# Commu02.net
KiCad netlist of a schematic drawn in Altium Designer
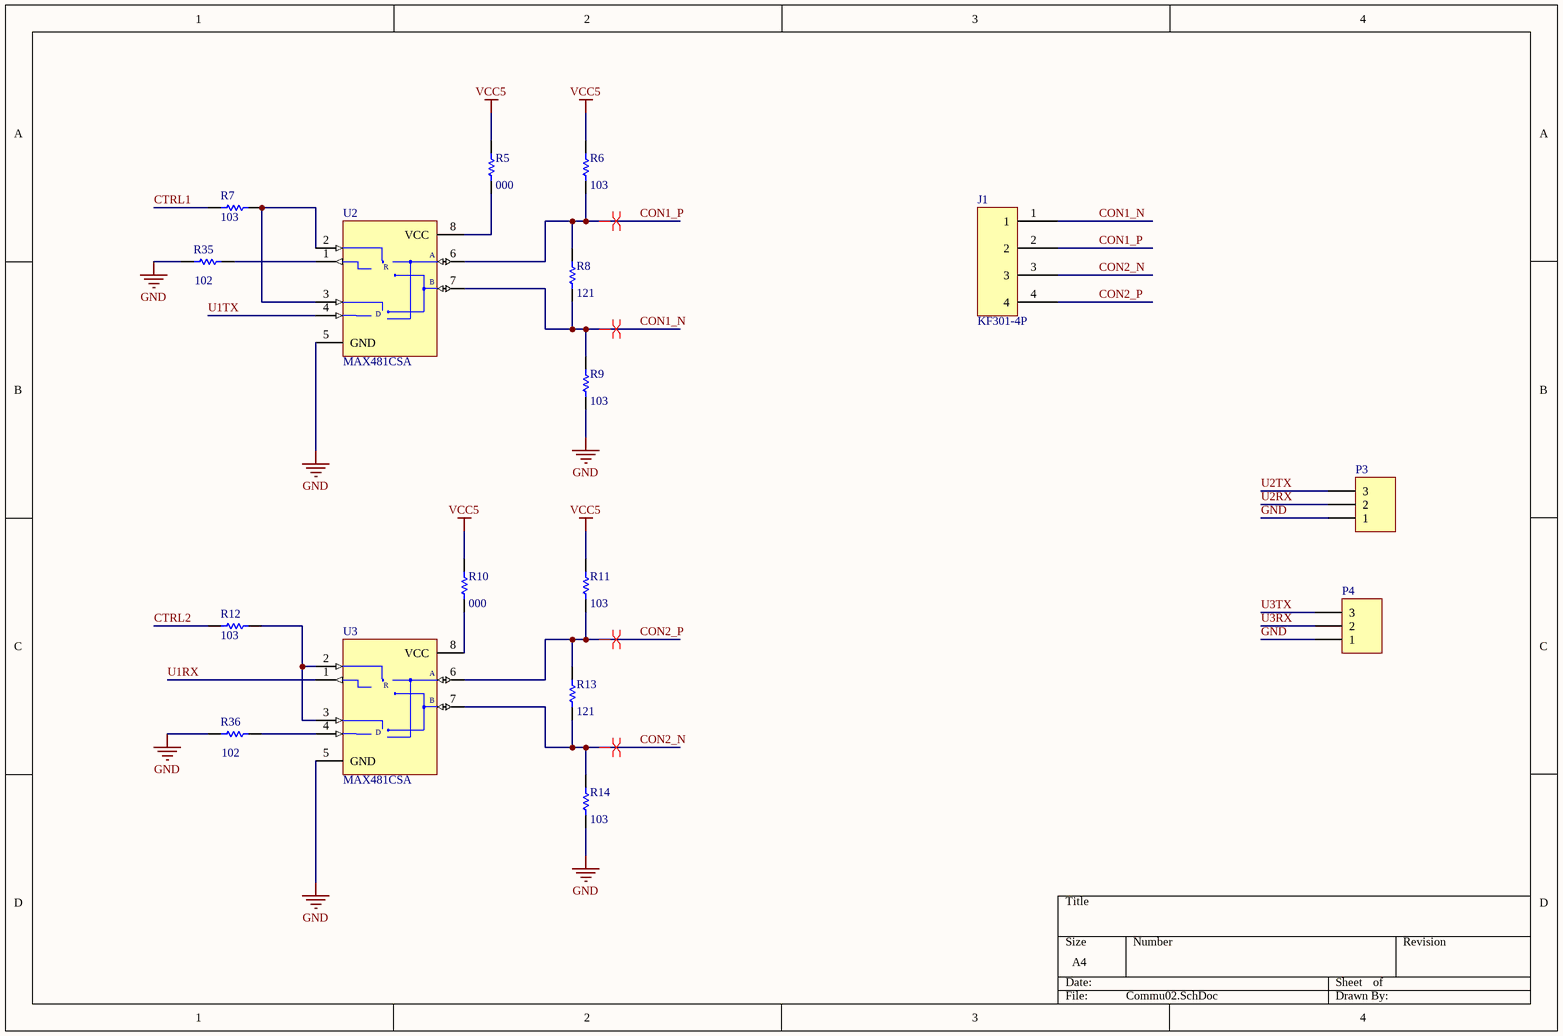
[diagram p0: Commu02.SchDoc]

(export (version "E")
  (design (tool "Eeschema 10.0.6"))
  (components
    (comp (ref "J1") (value "KF301-4P") (footprint "KF301-4P") (libsource (lib "CHK-I") (part "KF301-4P")))
    (comp (ref "P3")
      (value "Header 3")
      (footprint "HDR1X3")
      (description "Header, 3-Pin")
      (fields (field (name "PUBLISHER") "Altium Limited"))
      (libsource (lib "Miscellaneous Connectors") (part "Header 3"))
    )
    (comp (ref "P4")
      (value "Header 3")
      (footprint "HDR1X3")
      (description "Header, 3-Pin")
      (fields (field (name "PUBLISHER") "Altium Limited"))
      (libsource (lib "Miscellaneous Connectors") (part "Header 3"))
    )
    (comp (ref "R5")
      (value "000")
      (footprint "1206")
      (description "Semiconductor Resistor")
      (fields (field (name "Comment") "Res Semi") (field (name "PUBLISHER") "Altium Limited"))
      (libsource (lib "Miscellaneous Devices") (part "Res Semi"))
    )
    (comp (ref "R6")
      (value "103")
      (footprint "1206")
      (description "Semiconductor Resistor")
      (fields (field (name "Comment") "Res Semi") (field (name "PUBLISHER") "Altium Limited"))
      (libsource (lib "Miscellaneous Devices") (part "Res Semi"))
    )
    (comp (ref "R7")
      (value "103")
      (footprint "1206")
      (description "Semiconductor Resistor")
      (fields (field (name "Comment") "Res Semi") (field (name "PUBLISHER") "Altium Limited"))
      (libsource (lib "Miscellaneous Devices") (part "Res Semi"))
    )
    (comp (ref "R8")
      (value "121")
      (footprint "1206")
      (description "Semiconductor Resistor")
      (fields (field (name "Comment") "Res Semi") (field (name "PUBLISHER") "Altium Limited"))
      (libsource (lib "Miscellaneous Devices") (part "Res Semi"))
    )
    (comp (ref "R9")
      (value "103")
      (footprint "1206")
      (description "Semiconductor Resistor")
      (fields (field (name "Comment") "Res Semi") (field (name "PUBLISHER") "Altium Limited"))
      (libsource (lib "Miscellaneous Devices") (part "Res Semi"))
    )
    (comp (ref "R10")
      (value "000")
      (footprint "1206")
      (description "Semiconductor Resistor")
      (fields (field (name "Comment") "Res Semi") (field (name "PUBLISHER") "Altium Limited"))
      (libsource (lib "Miscellaneous Devices") (part "Res Semi"))
    )
    (comp (ref "R11")
      (value "103")
      (footprint "1206")
      (description "Semiconductor Resistor")
      (fields (field (name "Comment") "Res Semi") (field (name "PUBLISHER") "Altium Limited"))
      (libsource (lib "Miscellaneous Devices") (part "Res Semi"))
    )
    (comp (ref "R12")
      (value "103")
      (footprint "1206")
      (description "Semiconductor Resistor")
      (fields (field (name "Comment") "Res Semi") (field (name "PUBLISHER") "Altium Limited"))
      (libsource (lib "Miscellaneous Devices") (part "Res Semi"))
    )
    (comp (ref "R13")
      (value "121")
      (footprint "1206")
      (description "Semiconductor Resistor")
      (fields (field (name "Comment") "Res Semi") (field (name "PUBLISHER") "Altium Limited"))
      (libsource (lib "Miscellaneous Devices") (part "Res Semi"))
    )
    (comp (ref "R14")
      (value "103")
      (footprint "1206")
      (description "Semiconductor Resistor")
      (fields (field (name "Comment") "Res Semi") (field (name "PUBLISHER") "Altium Limited"))
      (libsource (lib "Miscellaneous Devices") (part "Res Semi"))
    )
    (comp (ref "R35")
      (value "102")
      (description "Semiconductor Resistor")
      (fields (field (name "Comment") "Res Semi") (field (name "PUBLISHER") "Altium Limited"))
      (libsource (lib "Miscellaneous Devices") (part "Res Semi"))
    )
    (comp (ref "R36")
      (value "102")
      (description "Semiconductor Resistor")
      (fields (field (name "Comment") "Res Semi") (field (name "PUBLISHER") "Altium Limited"))
      (libsource (lib "Miscellaneous Devices") (part "Res Semi"))
    )
    (comp (ref "U2")
      (value "MAX481CSA")
      (footprint "NSO8_M")
      (description "Low-Power, Slew-Rate-Limited RS-485/RS-422 Transceiver")
      (fields (field (name "PUBLISHER") "Altium Limited"))
      (libsource (lib "Maxim Communication Transceiver") (part "MAX481CSA"))
    )
    (comp (ref "U3")
      (value "MAX481CSA")
      (footprint "NSO8_M")
      (description "Low-Power, Slew-Rate-Limited RS-485/RS-422 Transceiver")
      (fields (field (name "PUBLISHER") "Altium Limited"))
      (libsource (lib "Maxim Communication Transceiver") (part "MAX481CSA"))
    )
  )
  (nets
    (net (code "1") (name "/CON1_N") (class "Default")
      (node (ref "J1") (pin "1") (pinfunction "1_1") (pintype "passive"))
      (node (ref "R8") (pin "1") (pinfunction "1_1") (pintype "passive"))
      (node (ref "R9") (pin "2") (pinfunction "2_2") (pintype "passive"))
      (node (ref "U2") (pin "7") (pinfunction "B_7") (pintype "bidirectional"))
    )
    (net (code "2") (name "/CON1_P") (class "Default")
      (node (ref "J1") (pin "2") (pinfunction "2_2") (pintype "passive"))
      (node (ref "R6") (pin "1") (pinfunction "1_1") (pintype "passive"))
      (node (ref "R8") (pin "2") (pinfunction "2_2") (pintype "passive"))
      (node (ref "U2") (pin "6") (pinfunction "A_6") (pintype "bidirectional"))
    )
    (net (code "3") (name "/CON2_N") (class "Default")
      (node (ref "J1") (pin "3") (pinfunction "3_3") (pintype "passive"))
      (node (ref "R13") (pin "1") (pinfunction "1_1") (pintype "passive"))
      (node (ref "R14") (pin "2") (pinfunction "2_2") (pintype "passive"))
      (node (ref "U3") (pin "7") (pinfunction "B_7") (pintype "bidirectional"))
    )
    (net (code "4") (name "/CON2_P") (class "Default")
      (node (ref "J1") (pin "4") (pinfunction "4_4") (pintype "passive"))
      (node (ref "R11") (pin "1") (pinfunction "1_1") (pintype "passive"))
      (node (ref "R13") (pin "2") (pinfunction "2_2") (pintype "passive"))
      (node (ref "U3") (pin "6") (pinfunction "A_6") (pintype "bidirectional"))
    )
    (net (code "5") (name "/CTRL1") (class "Default")
      (node (ref "R7") (pin "2") (pinfunction "2_2") (pintype "passive"))
    )
    (net (code "6") (name "/CTRL2") (class "Default")
      (node (ref "R12") (pin "2") (pinfunction "2_2") (pintype "passive"))
    )
    (net (code "7") (name "/U1RX") (class "Default")
      (node (ref "U3") (pin "1") (pinfunction "RO_1") (pintype "output"))
    )
    (net (code "8") (name "/U1TX") (class "Default")
      (node (ref "U2") (pin "4") (pinfunction "DI_4") (pintype "input"))
    )
    (net (code "9") (name "/U2RX") (class "Default")
      (node (ref "P3") (pin "2") (pinfunction "2_2") (pintype "passive"))
    )
    (net (code "10") (name "/U2TX") (class "Default")
      (node (ref "P3") (pin "3") (pinfunction "3_3") (pintype "passive"))
    )
    (net (code "11") (name "/U3RX") (class "Default")
      (node (ref "P4") (pin "2") (pinfunction "2_2") (pintype "passive"))
    )
    (net (code "12") (name "/U3TX") (class "Default")
      (node (ref "P4") (pin "3") (pinfunction "3_3") (pintype "passive"))
    )
    (net (code "13") (name "GND") (class "Default")
      (node (ref "P3") (pin "1") (pinfunction "1_1") (pintype "passive"))
      (node (ref "P4") (pin "1") (pinfunction "1_1") (pintype "passive"))
      (node (ref "R14") (pin "1") (pinfunction "1_1") (pintype "passive"))
      (node (ref "R35") (pin "2") (pinfunction "2_2") (pintype "passive"))
      (node (ref "R36") (pin "2") (pinfunction "2_2") (pintype "passive"))
      (node (ref "R9") (pin "1") (pinfunction "1_1") (pintype "passive"))
      (node (ref "U2") (pin "5") (pinfunction "GND_5") (pintype "power_in"))
      (node (ref "U3") (pin "5") (pinfunction "GND_5") (pintype "power_in"))
    )
    (net (code "14") (name "Net-(U2-DE)") (class "Default")
      (node (ref "R7") (pin "1") (pinfunction "1_1") (pintype "passive"))
      (node (ref "U2") (pin "2") (pinfunction "~{RE}_2") (pintype "input"))
      (node (ref "U2") (pin "3") (pinfunction "DE_3") (pintype "input"))
    )
    (net (code "15") (name "Net-(U2-RO)") (class "Default")
      (node (ref "R35") (pin "1") (pinfunction "1_1") (pintype "passive"))
      (node (ref "U2") (pin "1") (pinfunction "RO_1") (pintype "output"))
    )
    (net (code "16") (name "Net-(U2-VCC)") (class "Default")
      (node (ref "R5") (pin "1") (pinfunction "1_1") (pintype "passive"))
      (node (ref "U2") (pin "8") (pinfunction "VCC_8") (pintype "power_in"))
    )
    (net (code "17") (name "Net-(U3-DE)") (class "Default")
      (node (ref "R12") (pin "1") (pinfunction "1_1") (pintype "passive"))
      (node (ref "U3") (pin "2") (pinfunction "~{RE}_2") (pintype "input"))
      (node (ref "U3") (pin "3") (pinfunction "DE_3") (pintype "input"))
    )
    (net (code "18") (name "Net-(U3-DI)") (class "Default")
      (node (ref "R36") (pin "1") (pinfunction "1_1") (pintype "passive"))
      (node (ref "U3") (pin "4") (pinfunction "DI_4") (pintype "input"))
    )
    (net (code "19") (name "Net-(U3-VCC)") (class "Default")
      (node (ref "R10") (pin "1") (pinfunction "1_1") (pintype "passive"))
      (node (ref "U3") (pin "8") (pinfunction "VCC_8") (pintype "power_in"))
    )
    (net (code "20") (name "VCC5") (class "Default")
      (node (ref "R10") (pin "2") (pinfunction "2_2") (pintype "passive"))
      (node (ref "R11") (pin "2") (pinfunction "2_2") (pintype "passive"))
      (node (ref "R5") (pin "2") (pinfunction "2_2") (pintype "passive"))
      (node (ref "R6") (pin "2") (pinfunction "2_2") (pintype "passive"))
    )
  )
)
